# ladybug.net
KiCad netlist of a schematic drawn in EAGLE
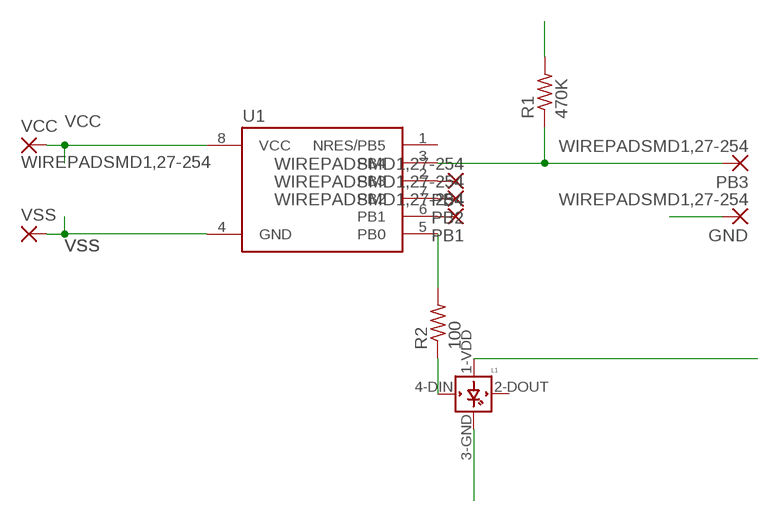
[diagram p0: schematic, sheet 1]

(export (version "E")
  (design (tool "Eeschema 10.0.6"))
  (components
    (comp (ref "GND")
      (value "WIREPADSMD1,27-254")
      (footprint "eagle-import:SMD1,27-2,54")
      (libsource (lib "eagle-import") (part "WIREPADSMD1,27-254"))
    )
    (comp (ref "L1")
      (value "WS2812B")
      (footprint "eagle-import:WS2812B")
      (libsource (lib "eagle-import") (part "WS2812B"))
    )
    (comp (ref "PB1")
      (value "WIREPADSMD1,27-254")
      (footprint "eagle-import:SMD1,27-2,54")
      (libsource (lib "eagle-import") (part "WIREPADSMD1,27-254"))
    )
    (comp (ref "PB2")
      (value "WIREPADSMD1,27-254")
      (footprint "eagle-import:SMD1,27-2,54")
      (libsource (lib "eagle-import") (part "WIREPADSMD1,27-254"))
    )
    (comp (ref "PB3")
      (value "WIREPADSMD1,27-254")
      (footprint "eagle-import:SMD1,27-2,54")
      (libsource (lib "eagle-import") (part "WIREPADSMD1,27-254"))
    )
    (comp (ref "PB4")
      (value "WIREPADSMD1,27-254")
      (footprint "eagle-import:SMD1,27-2,54")
      (libsource (lib "eagle-import") (part "WIREPADSMD1,27-254"))
    )
    (comp (ref "R1")
      (value "470K")
      (footprint "eagle-import:M1206")
      (libsource (lib "eagle-import") (part "R-US_M1206"))
    )
    (comp (ref "R2")
      (value "100")
      (footprint "eagle-import:M1206")
      (libsource (lib "eagle-import") (part "R-US_M1206"))
    )
    (comp (ref "U1")
      (value "ATTINY85-20S")
      (footprint "eagle-import:SOIC8_EIAJ_208MIL")
      (libsource (lib "eagle-import") (part "ATTINY85S-20"))
    )
    (comp (ref "VCC")
      (value "WIREPADSMD1,27-254")
      (footprint "eagle-import:SMD1,27-2,54")
      (libsource (lib "eagle-import") (part "WIREPADSMD1,27-254"))
    )
    (comp (ref "VSS")
      (value "WIREPADSMD1,27-254")
      (footprint "eagle-import:SMD1,27-2,54")
      (libsource (lib "eagle-import") (part "WIREPADSMD1,27-254"))
    )
  )
  (nets
    (net (code "1") (name "/VCC") (class "Default")
      (node (ref "L1") (pin "1-VDD") (pinfunction "VDD_1-VDD") (pintype "bidirectional"))
      (node (ref "R1") (pin "2") (pinfunction "2_2") (pintype "passive"))
      (node (ref "U1") (pin "8") (pinfunction "VCC_8") (pintype "power_in"))
      (node (ref "VCC") (pin "1") (pinfunction "P_1") (pintype "passive"))
    )
    (net (code "2") (name "/VSS") (class "Default")
      (node (ref "GND") (pin "1") (pinfunction "P_1") (pintype "passive"))
      (node (ref "L1") (pin "3-GND") (pinfunction "GND_3-GND") (pintype "bidirectional"))
      (node (ref "U1") (pin "4") (pinfunction "GND_4") (pintype "power_in"))
      (node (ref "VSS") (pin "1") (pinfunction "P_1") (pintype "passive"))
    )
    (net (code "3") (name "Net-(L1-DIN)") (class "Default")
      (node (ref "L1") (pin "4-DIN") (pinfunction "DIN_4-DIN") (pintype "input"))
      (node (ref "R2") (pin "1") (pinfunction "1_1") (pintype "passive"))
    )
    (net (code "4") (name "Net-(PB1-P)") (class "Default")
      (node (ref "PB1") (pin "1") (pinfunction "P_1") (pintype "passive"))
      (node (ref "U1") (pin "6") (pinfunction "PB1_6") (pintype "bidirectional"))
    )
    (net (code "5") (name "Net-(PB2-P)") (class "Default")
      (node (ref "PB2") (pin "1") (pinfunction "P_1") (pintype "passive"))
      (node (ref "U1") (pin "7") (pinfunction "PB2_7") (pintype "bidirectional"))
    )
    (net (code "6") (name "Net-(PB3-P)") (class "Default")
      (node (ref "PB3") (pin "1") (pinfunction "P_1") (pintype "passive"))
      (node (ref "R1") (pin "1") (pinfunction "1_1") (pintype "passive"))
      (node (ref "U1") (pin "3") (pinfunction "PB4_3") (pintype "bidirectional"))
    )
    (net (code "7") (name "Net-(PB4-P)") (class "Default")
      (node (ref "PB4") (pin "1") (pinfunction "P_1") (pintype "passive"))
      (node (ref "U1") (pin "2") (pinfunction "PB3_2") (pintype "bidirectional"))
    )
    (net (code "8") (name "Net-(U1-PB0)") (class "Default")
      (node (ref "R2") (pin "2") (pinfunction "2_2") (pintype "passive"))
      (node (ref "U1") (pin "5") (pinfunction "PB0_5") (pintype "bidirectional"))
    )
    (net (code "9") (name "unconnected-(L1-DOUT-Pad2-DOUT)") (class "Default")
      (node (ref "L1") (pin "2-DOUT") (pinfunction "DOUT_2-DOUT") (pintype "output"))
    )
    (net (code "10") (name "unconnected-(U1-NRES{slash}PB5-Pad1)") (class "Default")
      (node (ref "U1") (pin "1") (pinfunction "NRES/PB5_1") (pintype "bidirectional"))
    )
  )
)
